# design.net
KiCad netlist of a schematic drawn in Altium Designer
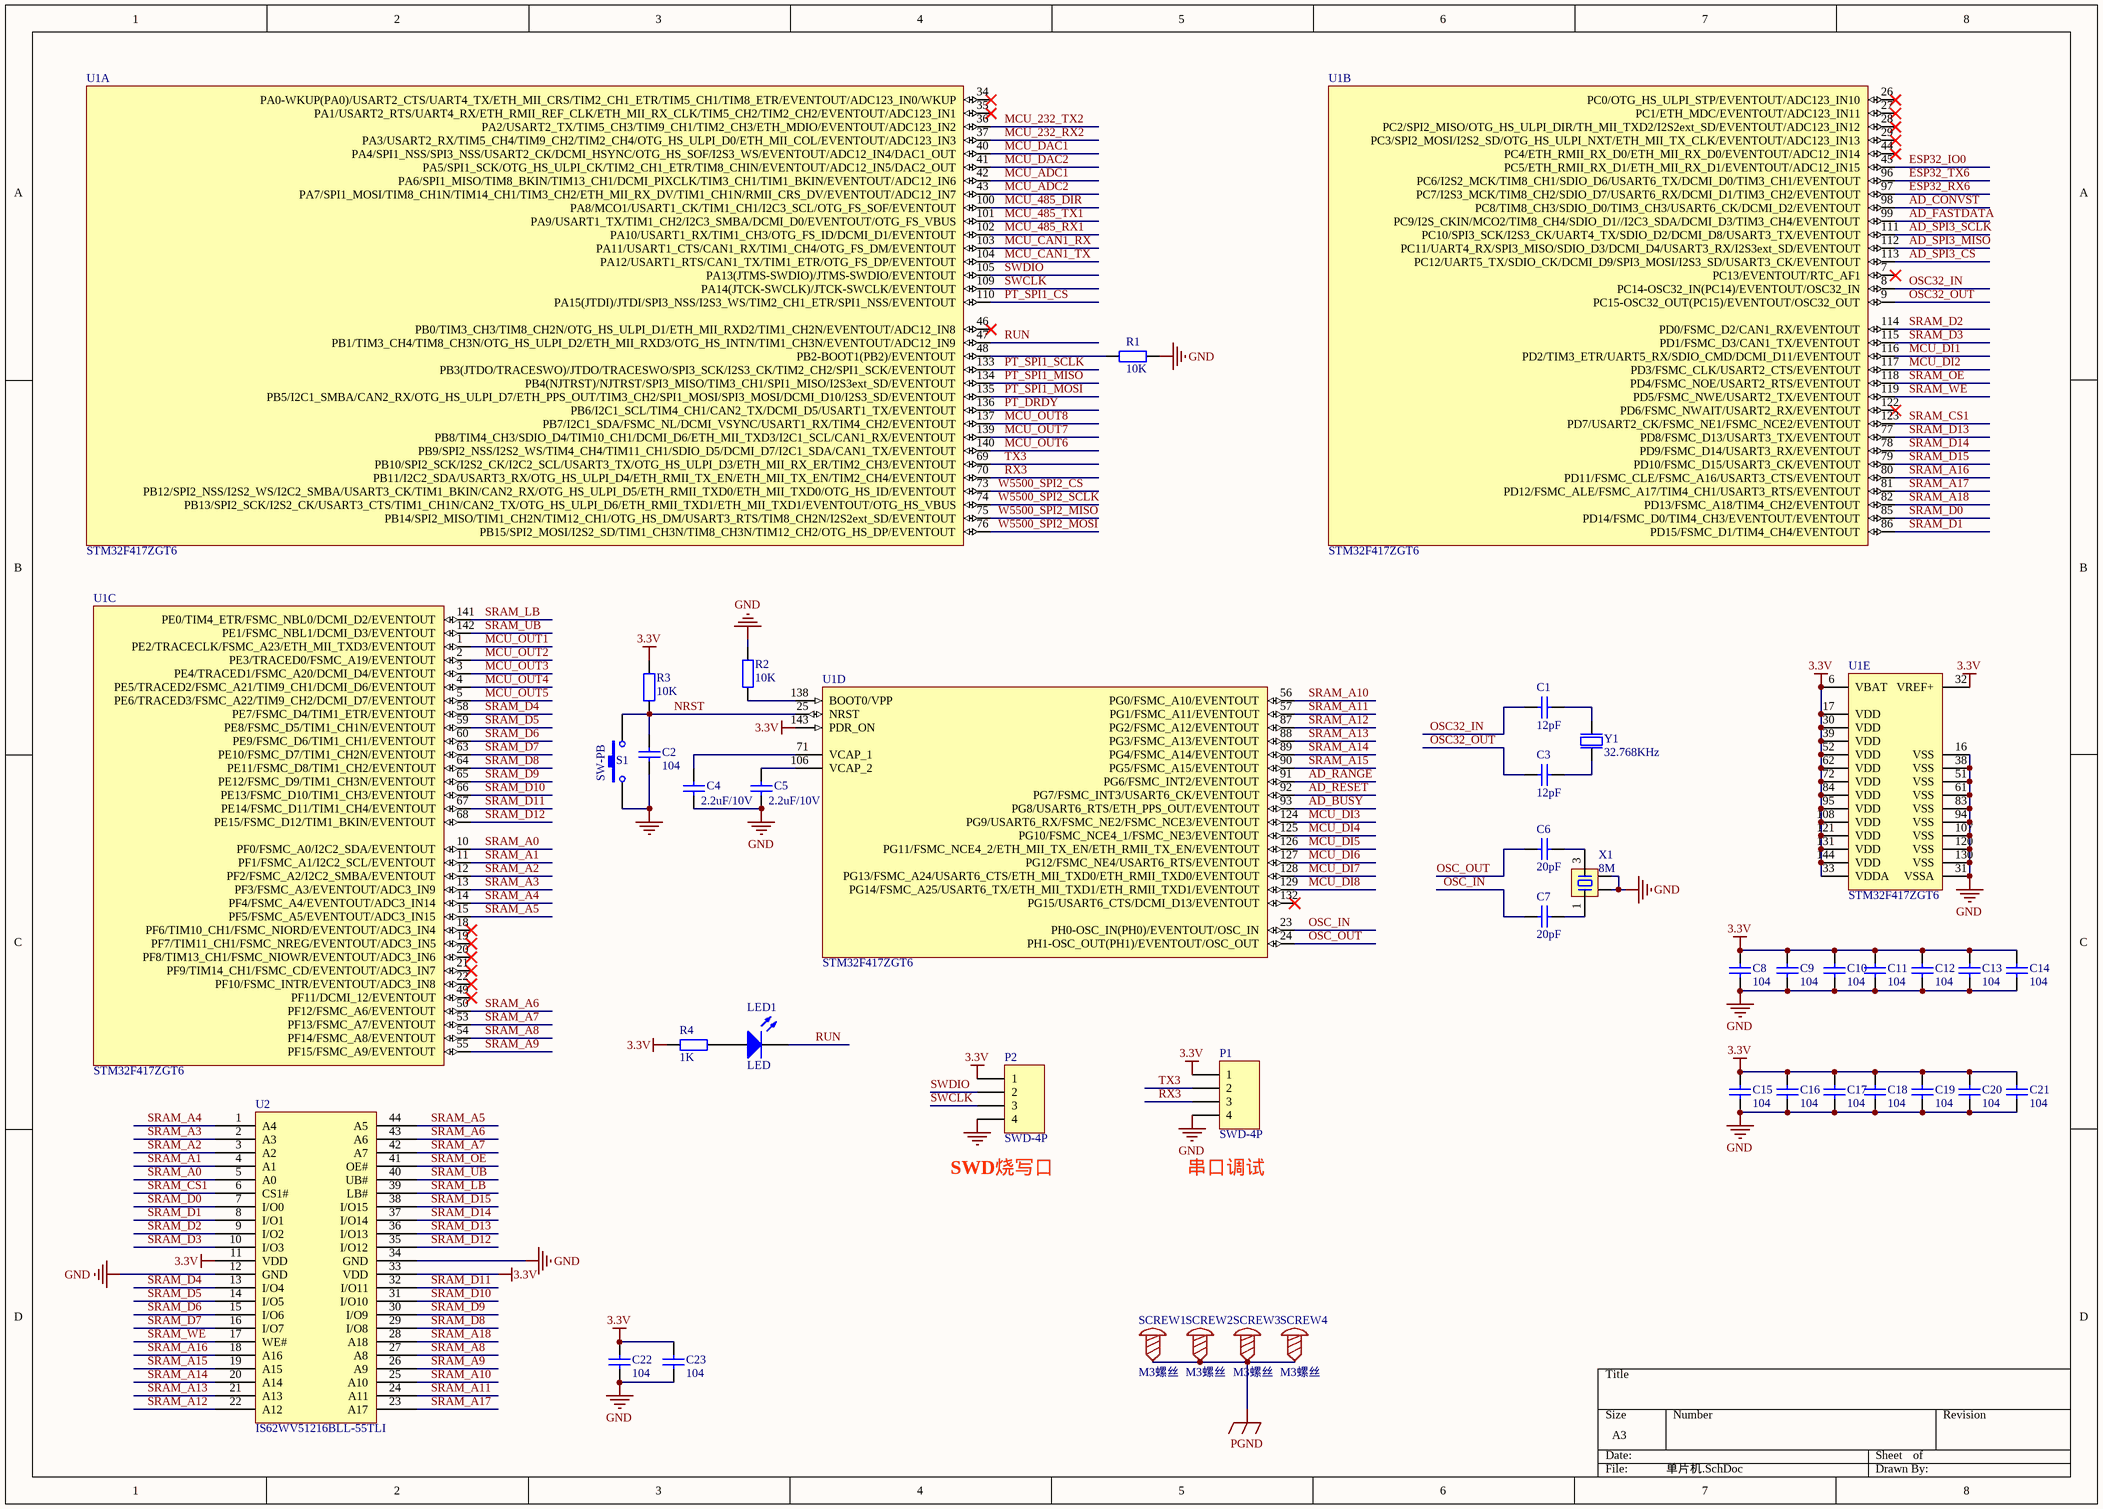
[diagram p0: 单片机.SchDoc]

(export (version "E")
  (design (tool "Eeschema 10.0.6"))
  (components
    (comp (ref "C1")
      (value "12pF")
      (footprint "C 0603_L")
      (description "0603贴片电容")
      (fields (field (name "PUBLISHER") "Altium Limited"))
      (libsource (lib "STM32_PLC_20251215") (part "Cap"))
    )
    (comp (ref "C2")
      (value "104")
      (footprint "C 0603_L")
      (description "0603贴片电容")
      (fields (field (name "PUBLISHER") "Altium Limited"))
      (libsource (lib "STM32_PLC_20251215") (part "Cap"))
    )
    (comp (ref "C3")
      (value "12pF")
      (footprint "C 0603_L")
      (description "0603贴片电容")
      (fields (field (name "PUBLISHER") "Altium Limited"))
      (libsource (lib "STM32_PLC_20251215") (part "Cap"))
    )
    (comp (ref "C4")
      (value "2.2uF/10V")
      (footprint "C 0603_L")
      (description "0603贴片电容")
      (fields (field (name "PUBLISHER") "Altium Limited"))
      (libsource (lib "STM32_PLC_20251215") (part "Cap"))
    )
    (comp (ref "C5")
      (value "2.2uF/10V")
      (footprint "C 0603_L")
      (description "0603贴片电容")
      (fields (field (name "PUBLISHER") "Altium Limited"))
      (libsource (lib "STM32_PLC_20251215") (part "Cap"))
    )
    (comp (ref "C6")
      (value "20pF")
      (footprint "C 0603_L")
      (description "0603贴片电容")
      (fields (field (name "PUBLISHER") "Altium Limited"))
      (libsource (lib "STM32_PLC_20251215") (part "Cap"))
    )
    (comp (ref "C7")
      (value "20pF")
      (footprint "C 0603_L")
      (description "0603贴片电容")
      (fields (field (name "PUBLISHER") "Altium Limited"))
      (libsource (lib "STM32_PLC_20251215") (part "Cap"))
    )
    (comp (ref "C8")
      (value "104")
      (footprint "C 0603_L")
      (description "0603贴片电容")
      (fields (field (name "PUBLISHER") "Altium Limited"))
      (libsource (lib "STM32_PLC_20251215") (part "Cap"))
    )
    (comp (ref "C9")
      (value "104")
      (footprint "C 0603_L")
      (description "0603贴片电容")
      (fields (field (name "PUBLISHER") "Altium Limited"))
      (libsource (lib "STM32_PLC_20251215") (part "Cap"))
    )
    (comp (ref "C10")
      (value "104")
      (footprint "C 0603_L")
      (description "0603贴片电容")
      (fields (field (name "PUBLISHER") "Altium Limited"))
      (libsource (lib "STM32_PLC_20251215") (part "Cap"))
    )
    (comp (ref "C11")
      (value "104")
      (footprint "C 0603_L")
      (description "0603贴片电容")
      (fields (field (name "PUBLISHER") "Altium Limited"))
      (libsource (lib "STM32_PLC_20251215") (part "Cap"))
    )
    (comp (ref "C12")
      (value "104")
      (footprint "C 0603_L")
      (description "0603贴片电容")
      (fields (field (name "PUBLISHER") "Altium Limited"))
      (libsource (lib "STM32_PLC_20251215") (part "Cap"))
    )
    (comp (ref "C13")
      (value "104")
      (footprint "C 0603_L")
      (description "0603贴片电容")
      (fields (field (name "PUBLISHER") "Altium Limited"))
      (libsource (lib "STM32_PLC_20251215") (part "Cap"))
    )
    (comp (ref "C14")
      (value "104")
      (footprint "C 0603_L")
      (description "0603贴片电容")
      (fields (field (name "PUBLISHER") "Altium Limited"))
      (libsource (lib "STM32_PLC_20251215") (part "Cap"))
    )
    (comp (ref "C15")
      (value "104")
      (footprint "C 0603_L")
      (description "0603贴片电容")
      (fields (field (name "PUBLISHER") "Altium Limited"))
      (libsource (lib "STM32_PLC_20251215") (part "Cap"))
    )
    (comp (ref "C16")
      (value "104")
      (footprint "C 0603_L")
      (description "0603贴片电容")
      (fields (field (name "PUBLISHER") "Altium Limited"))
      (libsource (lib "STM32_PLC_20251215") (part "Cap"))
    )
    (comp (ref "C17")
      (value "104")
      (footprint "C 0603_L")
      (description "0603贴片电容")
      (fields (field (name "PUBLISHER") "Altium Limited"))
      (libsource (lib "STM32_PLC_20251215") (part "Cap"))
    )
    (comp (ref "C18")
      (value "104")
      (footprint "C 0603_L")
      (description "0603贴片电容")
      (fields (field (name "PUBLISHER") "Altium Limited"))
      (libsource (lib "STM32_PLC_20251215") (part "Cap"))
    )
    (comp (ref "C19")
      (value "104")
      (footprint "C 0603_L")
      (description "0603贴片电容")
      (fields (field (name "PUBLISHER") "Altium Limited"))
      (libsource (lib "STM32_PLC_20251215") (part "Cap"))
    )
    (comp (ref "C20")
      (value "104")
      (footprint "C 0603_L")
      (description "0603贴片电容")
      (fields (field (name "PUBLISHER") "Altium Limited"))
      (libsource (lib "STM32_PLC_20251215") (part "Cap"))
    )
    (comp (ref "C21")
      (value "104")
      (footprint "C 0603_L")
      (description "0603贴片电容")
      (fields (field (name "PUBLISHER") "Altium Limited"))
      (libsource (lib "STM32_PLC_20251215") (part "Cap"))
    )
    (comp (ref "C22")
      (value "104")
      (footprint "C 0603_L")
      (description "0603贴片电容")
      (fields (field (name "PUBLISHER") "Altium Limited"))
      (libsource (lib "STM32_PLC_20251215") (part "Cap"))
    )
    (comp (ref "C23")
      (value "104")
      (footprint "C 0603_L")
      (description "0603贴片电容")
      (fields (field (name "PUBLISHER") "Altium Limited"))
      (libsource (lib "STM32_PLC_20251215") (part "Cap"))
    )
    (comp (ref "LED1")
      (value "LED")
      (footprint "LED 0603R")
      (description "0603发光二极管")
      (fields (field (name "PUBLISHER") "Altium Limited"))
      (libsource (lib "STM32_PLC_20251215") (part "LED"))
    )
    (comp (ref "P1")
      (value "SWD-4P")
      (footprint "DB-1X4")
      (description "2.54排针-4P")
      (fields (field (name "PUBLISHER") "Altium Limited"))
      (libsource (lib "STM32_PLC_20251215") (part "2.54排针-4P"))
    )
    (comp (ref "P2")
      (value "SWD-4P")
      (footprint "DB-1X4")
      (description "2.54排针-4P")
      (fields (field (name "PUBLISHER") "Altium Limited"))
      (libsource (lib "STM32_PLC_20251215") (part "2.54排针-4P"))
    )
    (comp (ref "R1")
      (value "10K")
      (footprint "R 0603_L")
      (description "0603贴片电阻")
      (fields (field (name "版权归属") "源创客"))
      (libsource (lib "STM32_PLC_20251215") (part "Res"))
    )
    (comp (ref "R2")
      (value "10K")
      (footprint "R 0603_L")
      (description "0603贴片电阻")
      (fields (field (name "版权归属") "源创客"))
      (libsource (lib "STM32_PLC_20251215") (part "Res"))
    )
    (comp (ref "R3")
      (value "10K")
      (footprint "R 0603_L")
      (description "C0603贴片电阻")
      (fields (field (name "版权归属") "源创客"))
      (libsource (lib "STM32_PLC_20251215") (part "Res"))
    )
    (comp (ref "R4")
      (value "1K")
      (footprint "R 0603_L")
      (description "C0603贴片电阻")
      (fields (field (name "版权归属") "源创客"))
      (libsource (lib "STM32_PLC_20251215") (part "Res"))
    )
    (comp (ref "S1")
      (value "SW-PB")
      (footprint "轻触按键3*4")
      (description "Switch")
      (fields (field (name "PUBLISHER") "Altium Limited"))
      (libsource (lib "红外能量舱") (part "SW-PB"))
    )
    (comp (ref "SCREW1")
      (value "M3螺丝")
      (footprint "螺丝孔")
      (libsource (lib "STM32F407_PLC_20260104_") (part "M3螺丝"))
    )
    (comp (ref "SCREW2")
      (value "M3螺丝")
      (footprint "螺丝孔")
      (libsource (lib "STM32F407_PLC_20260104_") (part "M3螺丝"))
    )
    (comp (ref "SCREW3")
      (value "M3螺丝")
      (footprint "螺丝孔")
      (libsource (lib "STM32F407_PLC_20260104_") (part "M3螺丝"))
    )
    (comp (ref "SCREW4")
      (value "M3螺丝")
      (footprint "螺丝孔")
      (libsource (lib "STM32F407_PLC_20260104_") (part "M3螺丝"))
    )
    (comp (ref "U1")
      (value "STM32F417ZGT6")
      (footprint "LQFP144 20X20_M")
      (libsource (lib "STM32F407_PLC_20260104_") (part "STM32F417ZGT6"))
    )
    (comp (ref "U2")
      (value "IS62WV51216BLL-55TLI")
      (footprint "TSOP-44_L18.4-W10.2-P0.80-LS11.8-BL")
      (fields (field (name "MANUFACTURER") "ISSI(美国芯成)"))
      (libsource (lib "STM32F407_PLC_20260104_") (part "IS62WV51216BLL-55TLI"))
    )
    (comp (ref "X1")
      (value "8M")
      (footprint "OSC 3225-4P")
      (description "4脚无源晶振")
      (fields (field (name "版权归属") "封装库来自淘宝卖家 ID：黄晶宝石"))
      (libsource (lib "STM32_PLC_20251215") (part "XTAL-4P"))
    )
    (comp (ref "Y1")
      (value "32.768KHz")
      (footprint "OSC 3215-2P")
      (fields
        (field (name "PART NUMBER") "XTAL SMD 12MHz (3225)")
        (field (name "MANUFACTURER") "TXC Corporation")
        (field (name "MANUFACTURER PART NUMBER") "7M-12.000MAAJ-T")
        (field (name "PUBLISHER") "Nordic Semiconductor")
      )
      (libsource (lib "wrhSchlib") (part "XTAL_3215"))
    )
  )
  (nets
    (net (code "1") (name "/AD_BUSY") (class "Default")
      (node (ref "U1") (pin "93") (pinfunction "PG8/USART6_RTS/ETH_PPS_OUT/EVENTOUT_93") (pintype "bidirectional"))
    )
    (net (code "2") (name "/AD_CONVST") (class "Default")
      (node (ref "U1") (pin "98") (pinfunction "PC8/TIM8_CH3/SDIO_D0/TIM3_CH3/USART6_CK/DCMI_D2/EVENTOUT_98") (pintype "bidirectional"))
    )
    (net (code "3") (name "/AD_FASTDATA") (class "Default")
      (node (ref "U1") (pin "99") (pinfunction "PC9/I2S_CKIN/MCO2/TIM8_CH4/SDIO_D1//I2C3_SDA/DCMI_D3/TIM3_CH4/EVENTOUT_99") (pintype "bidirectional"))
    )
    (net (code "4") (name "/AD_RANGE") (class "Default")
      (node (ref "U1") (pin "91") (pinfunction "PG6/FSMC_INT2/EVENTOUT_91") (pintype "bidirectional"))
    )
    (net (code "5") (name "/AD_RESET") (class "Default")
      (node (ref "U1") (pin "92") (pinfunction "PG7/FSMC_INT3/USART6_CK/EVENTOUT_92") (pintype "bidirectional"))
    )
    (net (code "6") (name "/AD_SPI3_CS") (class "Default")
      (node (ref "U1") (pin "113") (pinfunction "PC12/UART5_TX/SDIO_CK/DCMI_D9/SPI3_MOSI/I2S3_SD/USART3_CK/EVENTOUT_113") (pintype "bidirectional"))
    )
    (net (code "7") (name "/AD_SPI3_MISO") (class "Default")
      (node (ref "U1") (pin "112") (pinfunction "PC11/UART4_RX/SPI3_MISO/SDIO_D3/DCMI_D4/USART3_RX/I2S3ext_SD/EVENTOUT_112") (pintype "bidirectional"))
    )
    (net (code "8") (name "/AD_SPI3_SCLK") (class "Default")
      (node (ref "U1") (pin "111") (pinfunction "PC10/SPI3_SCK/I2S3_CK/UART4_TX/SDIO_D2/DCMI_D8/USART3_TX/EVENTOUT_111") (pintype "bidirectional"))
    )
    (net (code "9") (name "/ESP32_IO0") (class "Default")
      (node (ref "U1") (pin "45") (pinfunction "PC5/ETH_RMII_RX_D1/ETH_MII_RX_D1/EVENTOUT/ADC12_IN15_45") (pintype "bidirectional"))
    )
    (net (code "10") (name "/ESP32_RX6") (class "Default")
      (node (ref "U1") (pin "97") (pinfunction "PC7/I2S3_MCK/TIM8_CH2/SDIO_D7/USART6_RX/DCMI_D1/TIM3_CH2/EVENTOUT_97") (pintype "bidirectional"))
    )
    (net (code "11") (name "/ESP32_TX6") (class "Default")
      (node (ref "U1") (pin "96") (pinfunction "PC6/I2S2_MCK/TIM8_CH1/SDIO_D6/USART6_TX/DCMI_D0/TIM3_CH1/EVENTOUT_96") (pintype "bidirectional"))
    )
    (net (code "12") (name "/MCU_232_RX2") (class "Default")
      (node (ref "U1") (pin "37") (pinfunction "PA3/USART2_RX/TIM5_CH4/TIM9_CH2/TIM2_CH4/OTG_HS_ULPI_D0/ETH_MII_COL/EVENTOUT/ADC123_IN3_37") (pintype "bidirectional"))
    )
    (net (code "13") (name "/MCU_232_TX2") (class "Default")
      (node (ref "U1") (pin "36") (pinfunction "PA2/USART2_TX/TIM5_CH3/TIM9_CH1/TIM2_CH3/ETH_MDIO/EVENTOUT/ADC123_IN2_36") (pintype "bidirectional"))
    )
    (net (code "14") (name "/MCU_485_DIR") (class "Default")
      (node (ref "U1") (pin "100") (pinfunction "PA8/MCO1/USART1_CK/TIM1_CH1/I2C3_SCL/OTG_FS_SOF/EVENTOUT_100") (pintype "bidirectional"))
    )
    (net (code "15") (name "/MCU_485_RX1") (class "Default")
      (node (ref "U1") (pin "102") (pinfunction "PA10/USART1_RX/TIM1_CH3/OTG_FS_ID/DCMI_D1/EVENTOUT_102") (pintype "bidirectional"))
    )
    (net (code "16") (name "/MCU_485_TX1") (class "Default")
      (node (ref "U1") (pin "101") (pinfunction "PA9/USART1_TX/TIM1_CH2/I2C3_SMBA/DCMI_D0/EVENTOUT/OTG_FS_VBUS_101") (pintype "bidirectional"))
    )
    (net (code "17") (name "/MCU_ADC1") (class "Default")
      (node (ref "U1") (pin "42") (pinfunction "PA6/SPI1_MISO/TIM8_BKIN/TIM13_CH1/DCMI_PIXCLK/TIM3_CH1/TIM1_BKIN/EVENTOUT/ADC12_IN6_42") (pintype "bidirectional"))
    )
    (net (code "18") (name "/MCU_ADC2") (class "Default")
      (node (ref "U1") (pin "43") (pinfunction "PA7/SPI1_MOSI/TIM8_CH1N/TIM14_CH1/TIM3_CH2/ETH_MII_RX_DV/TIM1_CH1N/RMII_CRS_DV/EVENTOUT/ADC12_IN7_43") (pintype "bidirectional"))
    )
    (net (code "19") (name "/MCU_CAN1_RX") (class "Default")
      (node (ref "U1") (pin "103") (pinfunction "PA11/USART1_CTS/CAN1_RX/TIM1_CH4/OTG_FS_DM/EVENTOUT_103") (pintype "bidirectional"))
    )
    (net (code "20") (name "/MCU_CAN1_TX") (class "Default")
      (node (ref "U1") (pin "104") (pinfunction "PA12/USART1_RTS/CAN1_TX/TIM1_ETR/OTG_FS_DP/EVENTOUT_104") (pintype "bidirectional"))
    )
    (net (code "21") (name "/MCU_DAC1") (class "Default")
      (node (ref "U1") (pin "40") (pinfunction "PA4/SPI1_NSS/SPI3_NSS/USART2_CK/DCMI_HSYNC/OTG_HS_SOF/I2S3_WS/EVENTOUT/ADC12_IN4/DAC1_OUT_40") (pintype "bidirectional"))
    )
    (net (code "22") (name "/MCU_DAC2") (class "Default")
      (node (ref "U1") (pin "41") (pinfunction "PA5/SPI1_SCK/OTG_HS_ULPI_CK/TIM2_CH1_ETR/TIM8_CHIN/EVENTOUT/ADC12_IN5/DAC2_OUT_41") (pintype "bidirectional"))
    )
    (net (code "23") (name "/MCU_DI1") (class "Default")
      (node (ref "U1") (pin "116") (pinfunction "PD2/TIM3_ETR/UART5_RX/SDIO_CMD/DCMI_D11/EVENTOUT_116") (pintype "bidirectional"))
    )
    (net (code "24") (name "/MCU_DI2") (class "Default")
      (node (ref "U1") (pin "117") (pinfunction "PD3/FSMC_CLK/USART2_CTS/EVENTOUT_117") (pintype "bidirectional"))
    )
    (net (code "25") (name "/MCU_DI3") (class "Default")
      (node (ref "U1") (pin "124") (pinfunction "PG9/USART6_RX/FSMC_NE2/FSMC_NCE3/EVENTOUT_124") (pintype "bidirectional"))
    )
    (net (code "26") (name "/MCU_DI4") (class "Default")
      (node (ref "U1") (pin "125") (pinfunction "PG10/FSMC_NCE4_1/FSMC_NE3/EVENTOUT_125") (pintype "bidirectional"))
    )
    (net (code "27") (name "/MCU_DI5") (class "Default")
      (node (ref "U1") (pin "126") (pinfunction "PG11/FSMC_NCE4_2/ETH_MII_TX_EN/ETH_RMII_TX_EN/EVENTOUT_126") (pintype "bidirectional"))
    )
    (net (code "28") (name "/MCU_DI6") (class "Default")
      (node (ref "U1") (pin "127") (pinfunction "PG12/FSMC_NE4/USART6_RTS/EVENTOUT_127") (pintype "bidirectional"))
    )
    (net (code "29") (name "/MCU_DI7") (class "Default")
      (node (ref "U1") (pin "128") (pinfunction "PG13/FSMC_A24/USART6_CTS/ETH_MII_TXD0/ETH_RMII_TXD0/EVENTOUT_128") (pintype "bidirectional"))
    )
    (net (code "30") (name "/MCU_DI8") (class "Default")
      (node (ref "U1") (pin "129") (pinfunction "PG14/FSMC_A25/USART6_TX/ETH_MII_TXD1/ETH_RMII_TXD1/EVENTOUT_129") (pintype "bidirectional"))
    )
    (net (code "31") (name "/MCU_OUT1") (class "Default")
      (node (ref "U1") (pin "1") (pinfunction "PE2/TRACECLK/FSMC_A23/ETH_MII_TXD3/EVENTOUT_1") (pintype "bidirectional"))
    )
    (net (code "32") (name "/MCU_OUT2") (class "Default")
      (node (ref "U1") (pin "2") (pinfunction "PE3/TRACED0/FSMC_A19/EVENTOUT_2") (pintype "bidirectional"))
    )
    (net (code "33") (name "/MCU_OUT3") (class "Default")
      (node (ref "U1") (pin "3") (pinfunction "PE4/TRACED1/FSMC_A20/DCMI_D4/EVENTOUT_3") (pintype "bidirectional"))
    )
    (net (code "34") (name "/MCU_OUT4") (class "Default")
      (node (ref "U1") (pin "4") (pinfunction "PE5/TRACED2/FSMC_A21/TIM9_CH1/DCMI_D6/EVENTOUT_4") (pintype "bidirectional"))
    )
    (net (code "35") (name "/MCU_OUT5") (class "Default")
      (node (ref "U1") (pin "5") (pinfunction "PE6/TRACED3/FSMC_A22/TIM9_CH2/DCMI_D7/EVENTOUT_5") (pintype "bidirectional"))
    )
    (net (code "36") (name "/MCU_OUT6") (class "Default")
      (node (ref "U1") (pin "140") (pinfunction "PB9/SPI2_NSS/I2S2_WS/TIM4_CH4/TIM11_CH1/SDIO_D5/DCMI_D7/I2C1_SDA/CAN1_TX/EVENTOUT_140") (pintype "bidirectional"))
    )
    (net (code "37") (name "/MCU_OUT7") (class "Default")
      (node (ref "U1") (pin "139") (pinfunction "PB8/TIM4_CH3/SDIO_D4/TIM10_CH1/DCMI_D6/ETH_MII_TXD3/I2C1_SCL/CAN1_RX/EVENTOUT_139") (pintype "bidirectional"))
    )
    (net (code "38") (name "/MCU_OUT8") (class "Default")
      (node (ref "U1") (pin "137") (pinfunction "PB7/I2C1_SDA/FSMC_NL/DCMI_VSYNC/USART1_RX/TIM4_CH2/EVENTOUT_137") (pintype "bidirectional"))
    )
    (net (code "39") (name "/NRST") (class "Default")
      (node (ref "C2") (pin "2") (pinfunction "2_2") (pintype "passive"))
      (node (ref "R3") (pin "1") (pinfunction "1_1") (pintype "passive"))
      (node (ref "S1") (pin "2") (pinfunction "2_2") (pintype "passive"))
      (node (ref "U1") (pin "25") (pinfunction "NRST_25") (pintype "bidirectional"))
    )
    (net (code "40") (name "/OSC32_IN") (class "Default")
      (node (ref "C1") (pin "2") (pinfunction "2_2") (pintype "passive"))
      (node (ref "U1") (pin "8") (pinfunction "PC14-OSC32_IN(PC14)/EVENTOUT/OSC32_IN_8") (pintype "bidirectional"))
    )
    (net (code "41") (name "/OSC32_OUT") (class "Default")
      (node (ref "C3") (pin "2") (pinfunction "2_2") (pintype "passive"))
      (node (ref "U1") (pin "9") (pinfunction "PC15-OSC32_OUT(PC15)/EVENTOUT/OSC32_OUT_9") (pintype "bidirectional"))
    )
    (net (code "42") (name "/OSC_IN") (class "Default")
      (node (ref "C7") (pin "2") (pinfunction "2_2") (pintype "passive"))
      (node (ref "U1") (pin "23") (pinfunction "PH0-OSC_IN(PH0)/EVENTOUT/OSC_IN_23") (pintype "bidirectional"))
    )
    (net (code "43") (name "/OSC_OUT") (class "Default")
      (node (ref "C6") (pin "2") (pinfunction "2_2") (pintype "passive"))
      (node (ref "U1") (pin "24") (pinfunction "PH1-OSC_OUT(PH1)/EVENTOUT/OSC_OUT_24") (pintype "bidirectional"))
    )
    (net (code "44") (name "/PT_DRDY") (class "Default")
      (node (ref "U1") (pin "136") (pinfunction "PB6/I2C1_SCL/TIM4_CH1/CAN2_TX/DCMI_D5/USART1_TX/EVENTOUT_136") (pintype "bidirectional"))
    )
    (net (code "45") (name "/PT_SPI1_CS") (class "Default")
      (node (ref "U1") (pin "110") (pinfunction "PA15(JTDI)/JTDI/SPI3_NSS/I2S3_WS/TIM2_CH1_ETR/SPI1_NSS/EVENTOUT_110") (pintype "bidirectional"))
    )
    (net (code "46") (name "/PT_SPI1_MISO") (class "Default")
      (node (ref "U1") (pin "134") (pinfunction "PB4(NJTRST)/NJTRST/SPI3_MISO/TIM3_CH1/SPI1_MISO/I2S3ext_SD/EVENTOUT_134") (pintype "bidirectional"))
    )
    (net (code "47") (name "/PT_SPI1_MOSI") (class "Default")
      (node (ref "U1") (pin "135") (pinfunction "PB5/I2C1_SMBA/CAN2_RX/OTG_HS_ULPI_D7/ETH_PPS_OUT/TIM3_CH2/SPI1_MOSI/SPI3_MOSI/DCMI_D10/I2S3_SD/EVENTOUT_135") (pintype "bidirectional"))
    )
    (net (code "48") (name "/PT_SPI1_SCLK") (class "Default")
      (node (ref "U1") (pin "133") (pinfunction "PB3(JTDO/TRACESWO)/JTDO/TRACESWO/SPI3_SCK/I2S3_CK/TIM2_CH2/SPI1_SCK/EVENTOUT_133") (pintype "bidirectional"))
    )
    (net (code "49") (name "/RUN") (class "Default")
      (node (ref "LED1") (pin "2") (pinfunction "K_2") (pintype "passive"))
      (node (ref "U1") (pin "47") (pinfunction "PB1/TIM3_CH4/TIM8_CH3N/OTG_HS_ULPI_D2/ETH_MII_RXD3/OTG_HS_INTN/TIM1_CH3N/EVENTOUT/ADC12_IN9_47") (pintype "bidirectional"))
    )
    (net (code "50") (name "/RX3") (class "Default")
      (node (ref "P1") (pin "3") (pinfunction "3_3") (pintype "passive"))
      (node (ref "U1") (pin "70") (pinfunction "PB11/I2C2_SDA/USART3_RX/OTG_HS_ULPI_D4/ETH_RMII_TX_EN/ETH_MII_TX_EN/TIM2_CH4/EVENTOUT_70") (pintype "bidirectional"))
    )
    (net (code "51") (name "/SRAM_A0") (class "Default")
      (node (ref "U1") (pin "10") (pinfunction "PF0/FSMC_A0/I2C2_SDA/EVENTOUT_10") (pintype "bidirectional"))
      (node (ref "U2") (pin "5") (pinfunction "A0_5") (pintype "passive"))
    )
    (net (code "52") (name "/SRAM_A1") (class "Default")
      (node (ref "U1") (pin "11") (pinfunction "PF1/FSMC_A1/I2C2_SCL/EVENTOUT_11") (pintype "bidirectional"))
      (node (ref "U2") (pin "4") (pinfunction "A1_4") (pintype "passive"))
    )
    (net (code "53") (name "/SRAM_A2") (class "Default")
      (node (ref "U1") (pin "12") (pinfunction "PF2/FSMC_A2/I2C2_SMBA/EVENTOUT_12") (pintype "bidirectional"))
      (node (ref "U2") (pin "3") (pinfunction "A2_3") (pintype "passive"))
    )
    (net (code "54") (name "/SRAM_A3") (class "Default")
      (node (ref "U1") (pin "13") (pinfunction "PF3/FSMC_A3/EVENTOUT/ADC3_IN9_13") (pintype "bidirectional"))
      (node (ref "U2") (pin "2") (pinfunction "A3_2") (pintype "passive"))
    )
    (net (code "55") (name "/SRAM_A4") (class "Default")
      (node (ref "U1") (pin "14") (pinfunction "PF4/FSMC_A4/EVENTOUT/ADC3_IN14_14") (pintype "bidirectional"))
      (node (ref "U2") (pin "1") (pinfunction "A4_1") (pintype "passive"))
    )
    (net (code "56") (name "/SRAM_A5") (class "Default")
      (node (ref "U1") (pin "15") (pinfunction "PF5/FSMC_A5/EVENTOUT/ADC3_IN15_15") (pintype "bidirectional"))
      (node (ref "U2") (pin "44") (pinfunction "A5_44") (pintype "passive"))
    )
    (net (code "57") (name "/SRAM_A6") (class "Default")
      (node (ref "U1") (pin "50") (pinfunction "PF12/FSMC_A6/EVENTOUT_50") (pintype "bidirectional"))
      (node (ref "U2") (pin "43") (pinfunction "A6_43") (pintype "passive"))
    )
    (net (code "58") (name "/SRAM_A7") (class "Default")
      (node (ref "U1") (pin "53") (pinfunction "PF13/FSMC_A7/EVENTOUT_53") (pintype "bidirectional"))
      (node (ref "U2") (pin "42") (pinfunction "A7_42") (pintype "passive"))
    )
    (net (code "59") (name "/SRAM_A8") (class "Default")
      (node (ref "U1") (pin "54") (pinfunction "PF14/FSMC_A8/EVENTOUT_54") (pintype "bidirectional"))
      (node (ref "U2") (pin "27") (pinfunction "A8_27") (pintype "passive"))
    )
    (net (code "60") (name "/SRAM_A9") (class "Default")
      (node (ref "U1") (pin "55") (pinfunction "PF15/FSMC_A9/EVENTOUT_55") (pintype "bidirectional"))
      (node (ref "U2") (pin "26") (pinfunction "A9_26") (pintype "passive"))
    )
    (net (code "61") (name "/SRAM_A10") (class "Default")
      (node (ref "U1") (pin "56") (pinfunction "PG0/FSMC_A10/EVENTOUT_56") (pintype "bidirectional"))
      (node (ref "U2") (pin "25") (pinfunction "A10_25") (pintype "passive"))
    )
    (net (code "62") (name "/SRAM_A11") (class "Default")
      (node (ref "U1") (pin "57") (pinfunction "PG1/FSMC_A11/EVENTOUT_57") (pintype "bidirectional"))
      (node (ref "U2") (pin "24") (pinfunction "A11_24") (pintype "passive"))
    )
    (net (code "63") (name "/SRAM_A12") (class "Default")
      (node (ref "U1") (pin "87") (pinfunction "PG2/FSMC_A12/EVENTOUT_87") (pintype "bidirectional"))
      (node (ref "U2") (pin "22") (pinfunction "A12_22") (pintype "passive"))
    )
    (net (code "64") (name "/SRAM_A13") (class "Default")
      (node (ref "U1") (pin "88") (pinfunction "PG3/FSMC_A13/EVENTOUT_88") (pintype "bidirectional"))
      (node (ref "U2") (pin "21") (pinfunction "A13_21") (pintype "passive"))
    )
    (net (code "65") (name "/SRAM_A14") (class "Default")
      (node (ref "U1") (pin "89") (pinfunction "PG4/FSMC_A14/EVENTOUT_89") (pintype "bidirectional"))
      (node (ref "U2") (pin "20") (pinfunction "A14_20") (pintype "passive"))
    )
    (net (code "66") (name "/SRAM_A15") (class "Default")
      (node (ref "U1") (pin "90") (pinfunction "PG5/FSMC_A15/EVENTOUT_90") (pintype "bidirectional"))
      (node (ref "U2") (pin "19") (pinfunction "A15_19") (pintype "passive"))
    )
    (net (code "67") (name "/SRAM_A16") (class "Default")
      (node (ref "U1") (pin "80") (pinfunction "PD11/FSMC_CLE/FSMC_A16/USART3_CTS/EVENTOUT_80") (pintype "bidirectional"))
      (node (ref "U2") (pin "18") (pinfunction "A16_18") (pintype "passive"))
    )
    (net (code "68") (name "/SRAM_A17") (class "Default")
      (node (ref "U1") (pin "81") (pinfunction "PD12/FSMC_ALE/FSMC_A17/TIM4_CH1/USART3_RTS/EVENTOUT_81") (pintype "bidirectional"))
      (node (ref "U2") (pin "23") (pinfunction "A17_23") (pintype "passive"))
    )
    (net (code "69") (name "/SRAM_A18") (class "Default")
      (node (ref "U1") (pin "82") (pinfunction "PD13/FSMC_A18/TIM4_CH2/EVENTOUT_82") (pintype "bidirectional"))
      (node (ref "U2") (pin "28") (pinfunction "A18_28") (pintype "passive"))
    )
    (net (code "70") (name "/SRAM_CS1") (class "Default")
      (node (ref "U1") (pin "123") (pinfunction "PD7/USART2_CK/FSMC_NE1/FSMC_NCE2/EVENTOUT_123") (pintype "bidirectional"))
      (node (ref "U2") (pin "6") (pinfunction "CS1#_6") (pintype "passive"))
    )
    (net (code "71") (name "/SRAM_D0") (class "Default")
      (node (ref "U1") (pin "85") (pinfunction "PD14/FSMC_D0/TIM4_CH3/EVENTOUT/EVENTOUT_85") (pintype "bidirectional"))
      (node (ref "U2") (pin "7") (pinfunction "I/O0_7") (pintype "passive"))
    )
    (net (code "72") (name "/SRAM_D1") (class "Default")
      (node (ref "U1") (pin "86") (pinfunction "PD15/FSMC_D1/TIM4_CH4/EVENTOUT_86") (pintype "bidirectional"))
      (node (ref "U2") (pin "8") (pinfunction "I/O1_8") (pintype "passive"))
    )
    (net (code "73") (name "/SRAM_D2") (class "Default")
      (node (ref "U1") (pin "114") (pinfunction "PD0/FSMC_D2/CAN1_RX/EVENTOUT_114") (pintype "bidirectional"))
      (node (ref "U2") (pin "9") (pinfunction "I/O2_9") (pintype "passive"))
    )
    (net (code "74") (name "/SRAM_D3") (class "Default")
      (node (ref "U1") (pin "115") (pinfunction "PD1/FSMC_D3/CAN1_TX/EVENTOUT_115") (pintype "bidirectional"))
      (node (ref "U2") (pin "10") (pinfunction "I/O3_10") (pintype "passive"))
    )
    (net (code "75") (name "/SRAM_D4") (class "Default")
      (node (ref "U1") (pin "58") (pinfunction "PE7/FSMC_D4/TIM1_ETR/EVENTOUT_58") (pintype "bidirectional"))
      (node (ref "U2") (pin "13") (pinfunction "I/O4_13") (pintype "passive"))
    )
    (net (code "76") (name "/SRAM_D5") (class "Default")
      (node (ref "U1") (pin "59") (pinfunction "PE8/FSMC_D5/TIM1_CH1N/EVENTOUT_59") (pintype "bidirectional"))
      (node (ref "U2") (pin "14") (pinfunction "I/O5_14") (pintype "passive"))
    )
    (net (code "77") (name "/SRAM_D6") (class "Default")
      (node (ref "U1") (pin "60") (pinfunction "PE9/FSMC_D6/TIM1_CH1/EVENTOUT_60") (pintype "bidirectional"))
      (node (ref "U2") (pin "15") (pinfunction "I/O6_15") (pintype "passive"))
    )
    (net (code "78") (name "/SRAM_D7") (class "Default")
      (node (ref "U1") (pin "63") (pinfunction "PE10/FSMC_D7/TIM1_CH2N/EVENTOUT_63") (pintype "bidirectional"))
      (node (ref "U2") (pin "16") (pinfunction "I/O7_16") (pintype "passive"))
    )
    (net (code "79") (name "/SRAM_D8") (class "Default")
      (node (ref "U1") (pin "64") (pinfunction "PE11/FSMC_D8/TIM1_CH2/EVENTOUT_64") (pintype "bidirectional"))
      (node (ref "U2") (pin "29") (pinfunction "I/O8_29") (pintype "passive"))
    )
    (net (code "80") (name "/SRAM_D9") (class "Default")
      (node (ref "U1") (pin "65") (pinfunction "PE12/FSMC_D9/TIM1_CH3N/EVENTOUT_65") (pintype "bidirectional"))
      (node (ref "U2") (pin "30") (pinfunction "I/O9_30") (pintype "passive"))
    )
    (net (code "81") (name "/SRAM_D10") (class "Default")
      (node (ref "U1") (pin "66") (pinfunction "PE13/FSMC_D10/TIM1_CH3/EVENTOUT_66") (pintype "bidirectional"))
      (node (ref "U2") (pin "31") (pinfunction "I/O10_31") (pintype "passive"))
    )
    (net (code "82") (name "/SRAM_D11") (class "Default")
      (node (ref "U1") (pin "67") (pinfunction "PE14/FSMC_D11/TIM1_CH4/EVENTOUT_67") (pintype "bidirectional"))
      (node (ref "U2") (pin "32") (pinfunction "I/O11_32") (pintype "passive"))
    )
    (net (code "83") (name "/SRAM_D12") (class "Default")
      (node (ref "U1") (pin "68") (pinfunction "PE15/FSMC_D12/TIM1_BKIN/EVENTOUT_68") (pintype "bidirectional"))
      (node (ref "U2") (pin "35") (pinfunction "I/O12_35") (pintype "passive"))
    )
    (net (code "84") (name "/SRAM_D13") (class "Default")
      (node (ref "U1") (pin "77") (pinfunction "PD8/FSMC_D13/USART3_TX/EVENTOUT_77") (pintype "bidirectional"))
      (node (ref "U2") (pin "36") (pinfunction "I/O13_36") (pintype "passive"))
    )
    (net (code "85") (name "/SRAM_D14") (class "Default")
      (node (ref "U1") (pin "78") (pinfunction "PD9/FSMC_D14/USART3_RX/EVENTOUT_78") (pintype "bidirectional"))
      (node (ref "U2") (pin "37") (pinfunction "I/O14_37") (pintype "passive"))
    )
    (net (code "86") (name "/SRAM_D15") (class "Default")
      (node (ref "U1") (pin "79") (pinfunction "PD10/FSMC_D15/USART3_CK/EVENTOUT_79") (pintype "bidirectional"))
      (node (ref "U2") (pin "38") (pinfunction "I/O15_38") (pintype "passive"))
    )
    (net (code "87") (name "/SRAM_LB") (class "Default")
      (node (ref "U1") (pin "141") (pinfunction "PE0/TIM4_ETR/FSMC_NBL0/DCMI_D2/EVENTOUT_141") (pintype "bidirectional"))
      (node (ref "U2") (pin "39") (pinfunction "LB#_39") (pintype "passive"))
    )
    (net (code "88") (name "/SRAM_OE") (class "Default")
      (node (ref "U1") (pin "118") (pinfunction "PD4/FSMC_NOE/USART2_RTS/EVENTOUT_118") (pintype "bidirectional"))
      (node (ref "U2") (pin "41") (pinfunction "OE#_41") (pintype "passive"))
    )
    (net (code "89") (name "/SRAM_UB") (class "Default")
      (node (ref "U1") (pin "142") (pinfunction "PE1/FSMC_NBL1/DCMI_D3/EVENTOUT_142") (pintype "bidirectional"))
      (node (ref "U2") (pin "40") (pinfunction "UB#_40") (pintype "passive"))
    )
    (net (code "90") (name "/SRAM_WE") (class "Default")
      (node (ref "U1") (pin "119") (pinfunction "PD5/FSMC_NWE/USART2_TX/EVENTOUT_119") (pintype "bidirectional"))
      (node (ref "U2") (pin "17") (pinfunction "WE#_17") (pintype "passive"))
    )
    (net (code "91") (name "/SWCLK") (class "Default")
      (node (ref "P2") (pin "3") (pinfunction "3_3") (pintype "passive"))
      (node (ref "U1") (pin "109") (pinfunction "PA14(JTCK-SWCLK)/JTCK-SWCLK/EVENTOUT_109") (pintype "bidirectional"))
    )
    (net (code "92") (name "/SWDIO") (class "Default")
      (node (ref "P2") (pin "2") (pinfunction "2_2") (pintype "passive"))
      (node (ref "U1") (pin "105") (pinfunction "PA13(JTMS-SWDIO)/JTMS-SWDIO/EVENTOUT_105") (pintype "bidirectional"))
    )
    (net (code "93") (name "/TX3") (class "Default")
      (node (ref "P1") (pin "2") (pinfunction "2_2") (pintype "passive"))
      (node (ref "U1") (pin "69") (pinfunction "PB10/SPI2_SCK/I2S2_CK/I2C2_SCL/USART3_TX/OTG_HS_ULPI_D3/ETH_MII_RX_ER/TIM2_CH3/EVENTOUT_69") (pintype "bidirectional"))
    )
    (net (code "94") (name "/W5500_SPI2_CS") (class "Default")
      (node (ref "U1") (pin "73") (pinfunction "PB12/SPI2_NSS/I2S2_WS/I2C2_SMBA/USART3_CK/TIM1_BKIN/CAN2_RX/OTG_HS_ULPI_D5/ETH_RMII_TXD0/ETH_MII_TXD0/OTG_HS_ID/EVENTOUT_73") (pintype "bidirectional"))
    )
    (net (code "95") (name "/W5500_SPI2_MISO") (class "Default")
      (node (ref "U1") (pin "75") (pinfunction "PB14/SPI2_MISO/TIM1_CH2N/TIM12_CH1/OTG_HS_DM/USART3_RTS/TIM8_CH2N/I2S2ext_SD/EVENTOUT_75") (pintype "bidirectional"))
    )
    (net (code "96") (name "/W5500_SPI2_MOSI") (class "Default")
      (node (ref "U1") (pin "76") (pinfunction "PB15/SPI2_MOSI/I2S2_SD/TIM1_CH3N/TIM8_CH3N/TIM12_CH2/OTG_HS_DP/EVENTOUT_76") (pintype "bidirectional"))
    )
    (net (code "97") (name "/W5500_SPI2_SCLK") (class "Default")
      (node (ref "U1") (pin "74") (pinfunction "PB13/SPI2_SCK/I2S2_CK/USART3_CTS/TIM1_CH1N/CAN2_TX/OTG_HS_ULPI_D6/ETH_RMII_TXD1/ETH_MII_TXD1/EVENTOUT/OTG_HS_VBUS_74") (pintype "bidirectional"))
    )
    (net (code "98") (name "3.3V") (class "Default")
      (node (ref "C10") (pin "2") (pinfunction "2_2") (pintype "passive"))
      (node (ref "C11") (pin "2") (pinfunction "2_2") (pintype "passive"))
      (node (ref "C12") (pin "2") (pinfunction "2_2") (pintype "passive"))
      (node (ref "C13") (pin "2") (pinfunction "2_2") (pintype "passive"))
      (node (ref "C14") (pin "2") (pinfunction "2_2") (pintype "passive"))
      (node (ref "C15") (pin "2") (pinfunction "2_2") (pintype "passive"))
      (node (ref "C16") (pin "2") (pinfunction "2_2") (pintype "passive"))
      (node (ref "C17") (pin "2") (pinfunction "2_2") (pintype "passive"))
      (node (ref "C18") (pin "2") (pinfunction "2_2") (pintype "passive"))
      (node (ref "C19") (pin "2") (pinfunction "2_2") (pintype "passive"))
      (node (ref "C20") (pin "2") (pinfunction "2_2") (pintype "passive"))
      (node (ref "C21") (pin "2") (pinfunction "2_2") (pintype "passive"))
      (node (ref "C22") (pin "2") (pinfunction "2_2") (pintype "passive"))
      (node (ref "C23") (pin "2") (pinfunction "2_2") (pintype "passive"))
      (node (ref "C8") (pin "2") (pinfunction "2_2") (pintype "passive"))
      (node (ref "C9") (pin "2") (pinfunction "2_2") (pintype "passive"))
      (node (ref "P1") (pin "1") (pinfunction "1_1") (pintype "passive"))
      (node (ref "P2") (pin "1") (pinfunction "1_1") (pintype "passive"))
      (node (ref "R3") (pin "2") (pinfunction "2_2") (pintype "passive"))
      (node (ref "R4") (pin "1") (pinfunction "1_1") (pintype "passive"))
      (node (ref "U1") (pin "108") (pinfunction "VDD_108") (pintype "power_in"))
      (node (ref "U1") (pin "121") (pinfunction "VDD_121") (pintype "power_in"))
      (node (ref "U1") (pin "131") (pinfunction "VDD_131") (pintype "power_in"))
      (node (ref "U1") (pin "143") (pinfunction "PDR_ON_143") (pintype "input"))
      (node (ref "U1") (pin "144") (pinfunction "VDD_144") (pintype "power_in"))
      (node (ref "U1") (pin "17") (pinfunction "VDD_17") (pintype "power_in"))
      (node (ref "U1") (pin "30") (pinfunction "VDD_30") (pintype "power_in"))
      (node (ref "U1") (pin "32") (pinfunction "VREF+_32") (pintype "power_in"))
      (node (ref "U1") (pin "33") (pinfunction "VDDA_33") (pintype "power_in"))
      (node (ref "U1") (pin "39") (pinfunction "VDD_39") (pintype "power_in"))
      (node (ref "U1") (pin "52") (pinfunction "VDD_52") (pintype "power_in"))
      (node (ref "U1") (pin "6") (pinfunction "VBAT_6") (pintype "power_in"))
      (node (ref "U1") (pin "62") (pinfunction "VDD_62") (pintype "power_in"))
      (node (ref "U1") (pin "72") (pinfunction "VDD_72") (pintype "power_in"))
      (node (ref "U1") (pin "84") (pinfunction "VDD_84") (pintype "power_in"))
      (node (ref "U1") (pin "95") (pinfunction "VDD_95") (pintype "power_in"))
      (node (ref "U2") (pin "11") (pinfunction "VDD_11") (pintype "passive"))
      (node (ref "U2") (pin "33") (pinfunction "VDD_33") (pintype "passive"))
    )
    (net (code "99") (name "GND") (class "Default")
      (node (ref "C10") (pin "1") (pinfunction "1_1") (pintype "passive"))
      (node (ref "C11") (pin "1") (pinfunction "1_1") (pintype "passive"))
      (node (ref "C12") (pin "1") (pinfunction "1_1") (pintype "passive"))
      (node (ref "C13") (pin "1") (pinfunction "1_1") (pintype "passive"))
      (node (ref "C14") (pin "1") (pinfunction "1_1") (pintype "passive"))
      (node (ref "C15") (pin "1") (pinfunction "1_1") (pintype "passive"))
      (node (ref "C16") (pin "1") (pinfunction "1_1") (pintype "passive"))
      (node (ref "C17") (pin "1") (pinfunction "1_1") (pintype "passive"))
      (node (ref "C18") (pin "1") (pinfunction "1_1") (pintype "passive"))
      (node (ref "C19") (pin "1") (pinfunction "1_1") (pintype "passive"))
      (node (ref "C2") (pin "1") (pinfunction "1_1") (pintype "passive"))
      (node (ref "C20") (pin "1") (pinfunction "1_1") (pintype "passive"))
      (node (ref "C21") (pin "1") (pinfunction "1_1") (pintype "passive"))
      (node (ref "C22") (pin "1") (pinfunction "1_1") (pintype "passive"))
      (node (ref "C23") (pin "1") (pinfunction "1_1") (pintype "passive"))
      (node (ref "C4") (pin "2") (pinfunction "2_2") (pintype "passive"))
      (node (ref "C5") (pin "2") (pinfunction "2_2") (pintype "passive"))
      (node (ref "C8") (pin "1") (pinfunction "1_1") (pintype "passive"))
      (node (ref "C9") (pin "1") (pinfunction "1_1") (pintype "passive"))
      (node (ref "P1") (pin "4") (pinfunction "4_4") (pintype "passive"))
      (node (ref "P2") (pin "4") (pinfunction "4_4") (pintype "passive"))
      (node (ref "R1") (pin "1") (pinfunction "1_1") (pintype "passive"))
      (node (ref "R2") (pin "2") (pinfunction "2_2") (pintype "passive"))
      (node (ref "S1") (pin "1") (pinfunction "1_1") (pintype "passive"))
      (node (ref "U1") (pin "107") (pinfunction "VSS_107") (pintype "power_in"))
      (node (ref "U1") (pin "120") (pinfunction "VSS_120") (pintype "power_in"))
      (node (ref "U1") (pin "130") (pinfunction "VSS_130") (pintype "power_in"))
      (node (ref "U1") (pin "16") (pinfunction "VSS_16") (pintype "power_in"))
      (node (ref "U1") (pin "31") (pinfunction "VSSA_31") (pintype "power_in"))
      (node (ref "U1") (pin "38") (pinfunction "VSS_38") (pintype "power_in"))
      (node (ref "U1") (pin "51") (pinfunction "VSS_51") (pintype "power_in"))
      (node (ref "U1") (pin "61") (pinfunction "VSS_61") (pintype "power_in"))
      (node (ref "U1") (pin "83") (pinfunction "VSS_83") (pintype "power_in"))
      (node (ref "U1") (pin "94") (pinfunction "VSS_94") (pintype "power_in"))
      (node (ref "U2") (pin "12") (pinfunction "GND_12") (pintype "passive"))
      (node (ref "U2") (pin "34") (pinfunction "GND_34") (pintype "passive"))
      (node (ref "X1") (pin "2") (pinfunction "2_2") (pintype "passive"))
      (node (ref "X1") (pin "4") (pinfunction "4_4") (pintype "passive"))
    )
    (net (code "100") (name "Net-(C6-Pad1)") (class "Default")
      (node (ref "C6") (pin "1") (pinfunction "1_1") (pintype "passive"))
      (node (ref "X1") (pin "3") (pinfunction "3_3") (pintype "passive"))
    )
    (net (code "101") (name "Net-(C7-Pad1)") (class "Default")
      (node (ref "C7") (pin "1") (pinfunction "1_1") (pintype "passive"))
      (node (ref "X1") (pin "1") (pinfunction "1_1") (pintype "passive"))
    )
    (net (code "102") (name "Net-(LED1-A)") (class "Default")
      (node (ref "LED1") (pin "1") (pinfunction "A_1") (pintype "passive"))
      (node (ref "R4") (pin "2") (pinfunction "2_2") (pintype "passive"))
    )
    (net (code "103") (name "Net-(U1A-PB2-BOOT1(PB2){slash}EVENTOUT)") (class "Default")
      (node (ref "R1") (pin "2") (pinfunction "2_2") (pintype "passive"))
      (node (ref "U1") (pin "48") (pinfunction "PB2-BOOT1(PB2)/EVENTOUT_48") (pintype "bidirectional"))
    )
    (net (code "104") (name "Net-(U1D-BOOT0{slash}VPP)") (class "Default")
      (node (ref "R2") (pin "1") (pinfunction "1_1") (pintype "passive"))
      (node (ref "U1") (pin "138") (pinfunction "BOOT0/VPP_138") (pintype "input"))
    )
    (net (code "105") (name "Net-(U1D-VCAP_1)") (class "Default")
      (node (ref "C4") (pin "1") (pinfunction "1_1") (pintype "passive"))
      (node (ref "U1") (pin "71") (pinfunction "VCAP_1_71") (pintype "power_in"))
    )
    (net (code "106") (name "Net-(U1D-VCAP_2)") (class "Default")
      (node (ref "C5") (pin "1") (pinfunction "1_1") (pintype "passive"))
      (node (ref "U1") (pin "106") (pinfunction "VCAP_2_106") (pintype "power_in"))
    )
    (net (code "107") (name "Net-(Y1-inp)") (class "Default")
      (node (ref "C3") (pin "1") (pinfunction "1_1") (pintype "passive"))
      (node (ref "Y1") (pin "1") (pinfunction "inp_1") (pintype "passive"))
    )
    (net (code "108") (name "Net-(Y1-out)") (class "Default")
      (node (ref "C1") (pin "1") (pinfunction "1_1") (pintype "passive"))
      (node (ref "Y1") (pin "2") (pinfunction "out_2") (pintype "passive"))
    )
    (net (code "109") (name "PGND") (class "Default")
      (node (ref "SCREW1") (pin "1") (pinfunction "1_1") (pintype "passive"))
      (node (ref "SCREW2") (pin "1") (pinfunction "1_1") (pintype "passive"))
      (node (ref "SCREW3") (pin "1") (pinfunction "1_1") (pintype "passive"))
      (node (ref "SCREW4") (pin "1") (pinfunction "1_1") (pintype "passive"))
    )
    (net (code "110") (name "unconnected-(U1A-PA0-WKUP(PA0){slash}USART2_CTS{slash}UART4_TX{slash}ETH_MII_CRS{slash}TIM2_CH1_ETR{slash}TIM5_CH1{slash}TIM8_ETR{slash}EVENTOUT{slash}ADC123_IN0{slash}WKUP-Pad34)") (class "Default")
      (node (ref "U1") (pin "34") (pinfunction "PA0-WKUP(PA0)/USART2_CTS/UART4_TX/ETH_MII_CRS/TIM2_CH1_ETR/TIM5_CH1/TIM8_ETR/EVENTOUT/ADC123_IN0/WKUP_34") (pintype "bidirectional+no_connect"))
    )
    (net (code "111") (name "unconnected-(U1A-PA1{slash}USART2_RTS{slash}UART4_RX{slash}ETH_RMII_REF_CLK{slash}ETH_MII_RX_CLK{slash}TIM5_CH2{slash}TIM2_CH2{slash}EVENTOUT{slash}ADC123_IN1-Pad35)") (class "Default")
      (node (ref "U1") (pin "35") (pinfunction "PA1/USART2_RTS/UART4_RX/ETH_RMII_REF_CLK/ETH_MII_RX_CLK/TIM5_CH2/TIM2_CH2/EVENTOUT/ADC123_IN1_35") (pintype "bidirectional+no_connect"))
    )
    (net (code "112") (name "unconnected-(U1A-PB0{slash}TIM3_CH3{slash}TIM8_CH2N{slash}OTG_HS_ULPI_D1{slash}ETH_MII_RXD2{slash}TIM1_CH2N{slash}EVENTOUT{slash}ADC12_IN8-Pad46)") (class "Default")
      (node (ref "U1") (pin "46") (pinfunction "PB0/TIM3_CH3/TIM8_CH2N/OTG_HS_ULPI_D1/ETH_MII_RXD2/TIM1_CH2N/EVENTOUT/ADC12_IN8_46") (pintype "bidirectional+no_connect"))
    )
    (net (code "113") (name "unconnected-(U1B-PC0{slash}OTG_HS_ULPI_STP{slash}EVENTOUT{slash}ADC123_IN10-Pad26)") (class "Default")
      (node (ref "U1") (pin "26") (pinfunction "PC0/OTG_HS_ULPI_STP/EVENTOUT/ADC123_IN10_26") (pintype "bidirectional+no_connect"))
    )
    (net (code "114") (name "unconnected-(U1B-PC1{slash}ETH_MDC{slash}EVENTOUT{slash}ADC123_IN11-Pad27)") (class "Default")
      (node (ref "U1") (pin "27") (pinfunction "PC1/ETH_MDC/EVENTOUT/ADC123_IN11_27") (pintype "bidirectional+no_connect"))
    )
    (net (code "115") (name "unconnected-(U1B-PC2{slash}SPI2_MISO{slash}OTG_HS_ULPI_DIR{slash}TH_MII_TXD2{slash}I2S2ext_SD{slash}EVENTOUT{slash}ADC123_IN12-Pad28)") (class "Default")
      (node (ref "U1") (pin "28") (pinfunction "PC2/SPI2_MISO/OTG_HS_ULPI_DIR/TH_MII_TXD2/I2S2ext_SD/EVENTOUT/ADC123_IN12_28") (pintype "bidirectional+no_connect"))
    )
    (net (code "116") (name "unconnected-(U1B-PC3{slash}SPI2_MOSI{slash}I2S2_SD{slash}OTG_HS_ULPI_NXT{slash}ETH_MII_TX_CLK{slash}EVENTOUT{slash}ADC123_IN13-Pad29)") (class "Default")
      (node (ref "U1") (pin "29") (pinfunction "PC3/SPI2_MOSI/I2S2_SD/OTG_HS_ULPI_NXT/ETH_MII_TX_CLK/EVENTOUT/ADC123_IN13_29") (pintype "bidirectional+no_connect"))
    )
    (net (code "117") (name "unconnected-(U1B-PC4{slash}ETH_RMII_RX_D0{slash}ETH_MII_RX_D0{slash}EVENTOUT{slash}ADC12_IN14-Pad44)") (class "Default")
      (node (ref "U1") (pin "44") (pinfunction "PC4/ETH_RMII_RX_D0/ETH_MII_RX_D0/EVENTOUT/ADC12_IN14_44") (pintype "bidirectional+no_connect"))
    )
    (net (code "118") (name "unconnected-(U1B-PC13{slash}EVENTOUT{slash}RTC_AF1-Pad7)") (class "Default")
      (node (ref "U1") (pin "7") (pinfunction "PC13/EVENTOUT/RTC_AF1_7") (pintype "bidirectional+no_connect"))
    )
    (net (code "119") (name "unconnected-(U1B-PD6{slash}FSMC_NWAIT{slash}USART2_RX{slash}EVENTOUT-Pad122)") (class "Default")
      (node (ref "U1") (pin "122") (pinfunction "PD6/FSMC_NWAIT/USART2_RX/EVENTOUT_122") (pintype "bidirectional+no_connect"))
    )
    (net (code "120") (name "unconnected-(U1C-PF6{slash}TIM10_CH1{slash}FSMC_NIORD{slash}EVENTOUT{slash}ADC3_IN4-Pad18)") (class "Default")
      (node (ref "U1") (pin "18") (pinfunction "PF6/TIM10_CH1/FSMC_NIORD/EVENTOUT/ADC3_IN4_18") (pintype "bidirectional+no_connect"))
    )
    (net (code "121") (name "unconnected-(U1C-PF7{slash}TIM11_CH1{slash}FSMC_NREG{slash}EVENTOUT{slash}ADC3_IN5-Pad19)") (class "Default")
      (node (ref "U1") (pin "19") (pinfunction "PF7/TIM11_CH1/FSMC_NREG/EVENTOUT/ADC3_IN5_19") (pintype "bidirectional+no_connect"))
    )
    (net (code "122") (name "unconnected-(U1C-PF8{slash}TIM13_CH1{slash}FSMC_NIOWR{slash}EVENTOUT{slash}ADC3_IN6-Pad20)") (class "Default")
      (node (ref "U1") (pin "20") (pinfunction "PF8/TIM13_CH1/FSMC_NIOWR/EVENTOUT/ADC3_IN6_20") (pintype "bidirectional+no_connect"))
    )
    (net (code "123") (name "unconnected-(U1C-PF9{slash}TIM14_CH1{slash}FSMC_CD{slash}EVENTOUT{slash}ADC3_IN7-Pad21)") (class "Default")
      (node (ref "U1") (pin "21") (pinfunction "PF9/TIM14_CH1/FSMC_CD/EVENTOUT/ADC3_IN7_21") (pintype "bidirectional+no_connect"))
    )
    (net (code "124") (name "unconnected-(U1C-PF10{slash}FSMC_INTR{slash}EVENTOUT{slash}ADC3_IN8-Pad22)") (class "Default")
      (node (ref "U1") (pin "22") (pinfunction "PF10/FSMC_INTR/EVENTOUT/ADC3_IN8_22") (pintype "bidirectional+no_connect"))
    )
    (net (code "125") (name "unconnected-(U1C-PF11{slash}DCMI_12{slash}EVENTOUT-Pad49)") (class "Default")
      (node (ref "U1") (pin "49") (pinfunction "PF11/DCMI_12/EVENTOUT_49") (pintype "bidirectional+no_connect"))
    )
    (net (code "126") (name "unconnected-(U1D-PG15{slash}USART6_CTS{slash}DCMI_D13{slash}EVENTOUT-Pad132)") (class "Default")
      (node (ref "U1") (pin "132") (pinfunction "PG15/USART6_CTS/DCMI_D13/EVENTOUT_132") (pintype "bidirectional+no_connect"))
    )
  )
)
